# modulo_extension_schdoc.net
KiCad netlist of a schematic drawn in Altium Designer
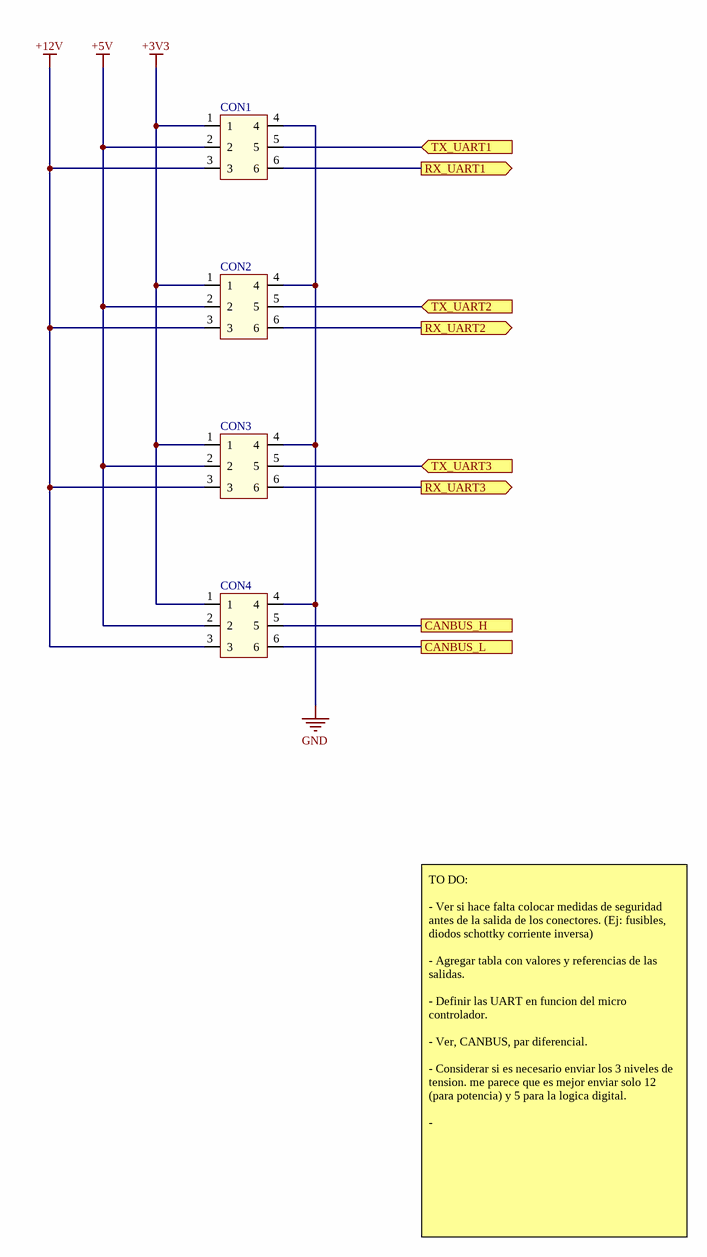
[diagram p0: modulo_extension_schdoc.SchDoc]

(export (version "E")
  (design (tool "Eeschema 10.0.6"))
  (components
    (comp (ref "CON1")
      (value "CONN_HEADER_RA_6POS")
      (footprint "CONN_HEADER_RA_6POS")
      (description "Conector hembra de 6 posiciones molex")
      (fields (field (name "MANUFACTURER") "Molex") (field (name "MANUFACTURER PART NUMBER") "45732-0001"))
      (libsource (lib "schlib_modulo_extensiones") (part "CONN_HEADER_RA_6POS"))
    )
    (comp (ref "CON2")
      (value "CONN_HEADER_RA_6POS")
      (footprint "CONN_HEADER_RA_6POS")
      (description "Conector hembra de 6 posiciones molex")
      (fields (field (name "MANUFACTURER") "Molex") (field (name "MANUFACTURER PART NUMBER") "45732-0001"))
      (libsource (lib "schlib_modulo_extensiones") (part "CONN_HEADER_RA_6POS"))
    )
    (comp (ref "CON3")
      (value "CONN_HEADER_RA_6POS")
      (footprint "CONN_HEADER_RA_6POS")
      (description "Conector hembra de 6 posiciones molex")
      (fields (field (name "MANUFACTURER") "Molex") (field (name "MANUFACTURER PART NUMBER") "45732-0001"))
      (libsource (lib "schlib_modulo_extensiones") (part "CONN_HEADER_RA_6POS"))
    )
    (comp (ref "CON4")
      (value "CONN_HEADER_RA_6POS")
      (footprint "CONN_HEADER_RA_6POS")
      (description "Conector hembra de 6 posiciones molex")
      (fields (field (name "MANUFACTURER") "Molex") (field (name "MANUFACTURER PART NUMBER") "45732-0001"))
      (libsource (lib "schlib_modulo_extensiones") (part "CONN_HEADER_RA_6POS"))
    )
  )
  (nets
    (net (code "1") (name "+3V3") (class "Default")
      (node (ref "CON1") (pin "1") (pinfunction "1_1") (pintype "passive"))
      (node (ref "CON2") (pin "1") (pinfunction "1_1") (pintype "passive"))
      (node (ref "CON3") (pin "1") (pinfunction "1_1") (pintype "passive"))
      (node (ref "CON4") (pin "1") (pinfunction "1_1") (pintype "passive"))
    )
    (net (code "2") (name "+5V") (class "Default")
      (node (ref "CON1") (pin "2") (pinfunction "2_2") (pintype "passive"))
      (node (ref "CON2") (pin "2") (pinfunction "2_2") (pintype "passive"))
      (node (ref "CON3") (pin "2") (pinfunction "2_2") (pintype "passive"))
      (node (ref "CON4") (pin "2") (pinfunction "2_2") (pintype "passive"))
    )
    (net (code "3") (name "+12V") (class "Default")
      (node (ref "CON1") (pin "3") (pinfunction "3_3") (pintype "passive"))
      (node (ref "CON2") (pin "3") (pinfunction "3_3") (pintype "passive"))
      (node (ref "CON3") (pin "3") (pinfunction "3_3") (pintype "passive"))
      (node (ref "CON4") (pin "3") (pinfunction "3_3") (pintype "passive"))
    )
    (net (code "4") (name "/CANBUS_H") (class "Default")
      (node (ref "CON4") (pin "5") (pinfunction "5_5") (pintype "passive"))
    )
    (net (code "5") (name "/CANBUS_L") (class "Default")
      (node (ref "CON4") (pin "6") (pinfunction "6_6") (pintype "passive"))
    )
    (net (code "6") (name "/RX_UART1") (class "Default")
      (node (ref "CON1") (pin "6") (pinfunction "6_6") (pintype "passive"))
    )
    (net (code "7") (name "/RX_UART2") (class "Default")
      (node (ref "CON2") (pin "6") (pinfunction "6_6") (pintype "passive"))
    )
    (net (code "8") (name "/RX_UART3") (class "Default")
      (node (ref "CON3") (pin "6") (pinfunction "6_6") (pintype "passive"))
    )
    (net (code "9") (name "/TX_UART1") (class "Default")
      (node (ref "CON1") (pin "5") (pinfunction "5_5") (pintype "passive"))
    )
    (net (code "10") (name "/TX_UART2") (class "Default")
      (node (ref "CON2") (pin "5") (pinfunction "5_5") (pintype "passive"))
    )
    (net (code "11") (name "/TX_UART3") (class "Default")
      (node (ref "CON3") (pin "5") (pinfunction "5_5") (pintype "passive"))
    )
    (net (code "12") (name "GND") (class "Default")
      (node (ref "CON1") (pin "4") (pinfunction "4_4") (pintype "passive"))
      (node (ref "CON2") (pin "4") (pinfunction "4_4") (pintype "passive"))
      (node (ref "CON3") (pin "4") (pinfunction "4_4") (pintype "passive"))
      (node (ref "CON4") (pin "4") (pinfunction "4_4") (pintype "passive"))
    )
  )
)
